# Sheet_1.net
KiCad netlist of a schematic drawn in EasyEDA
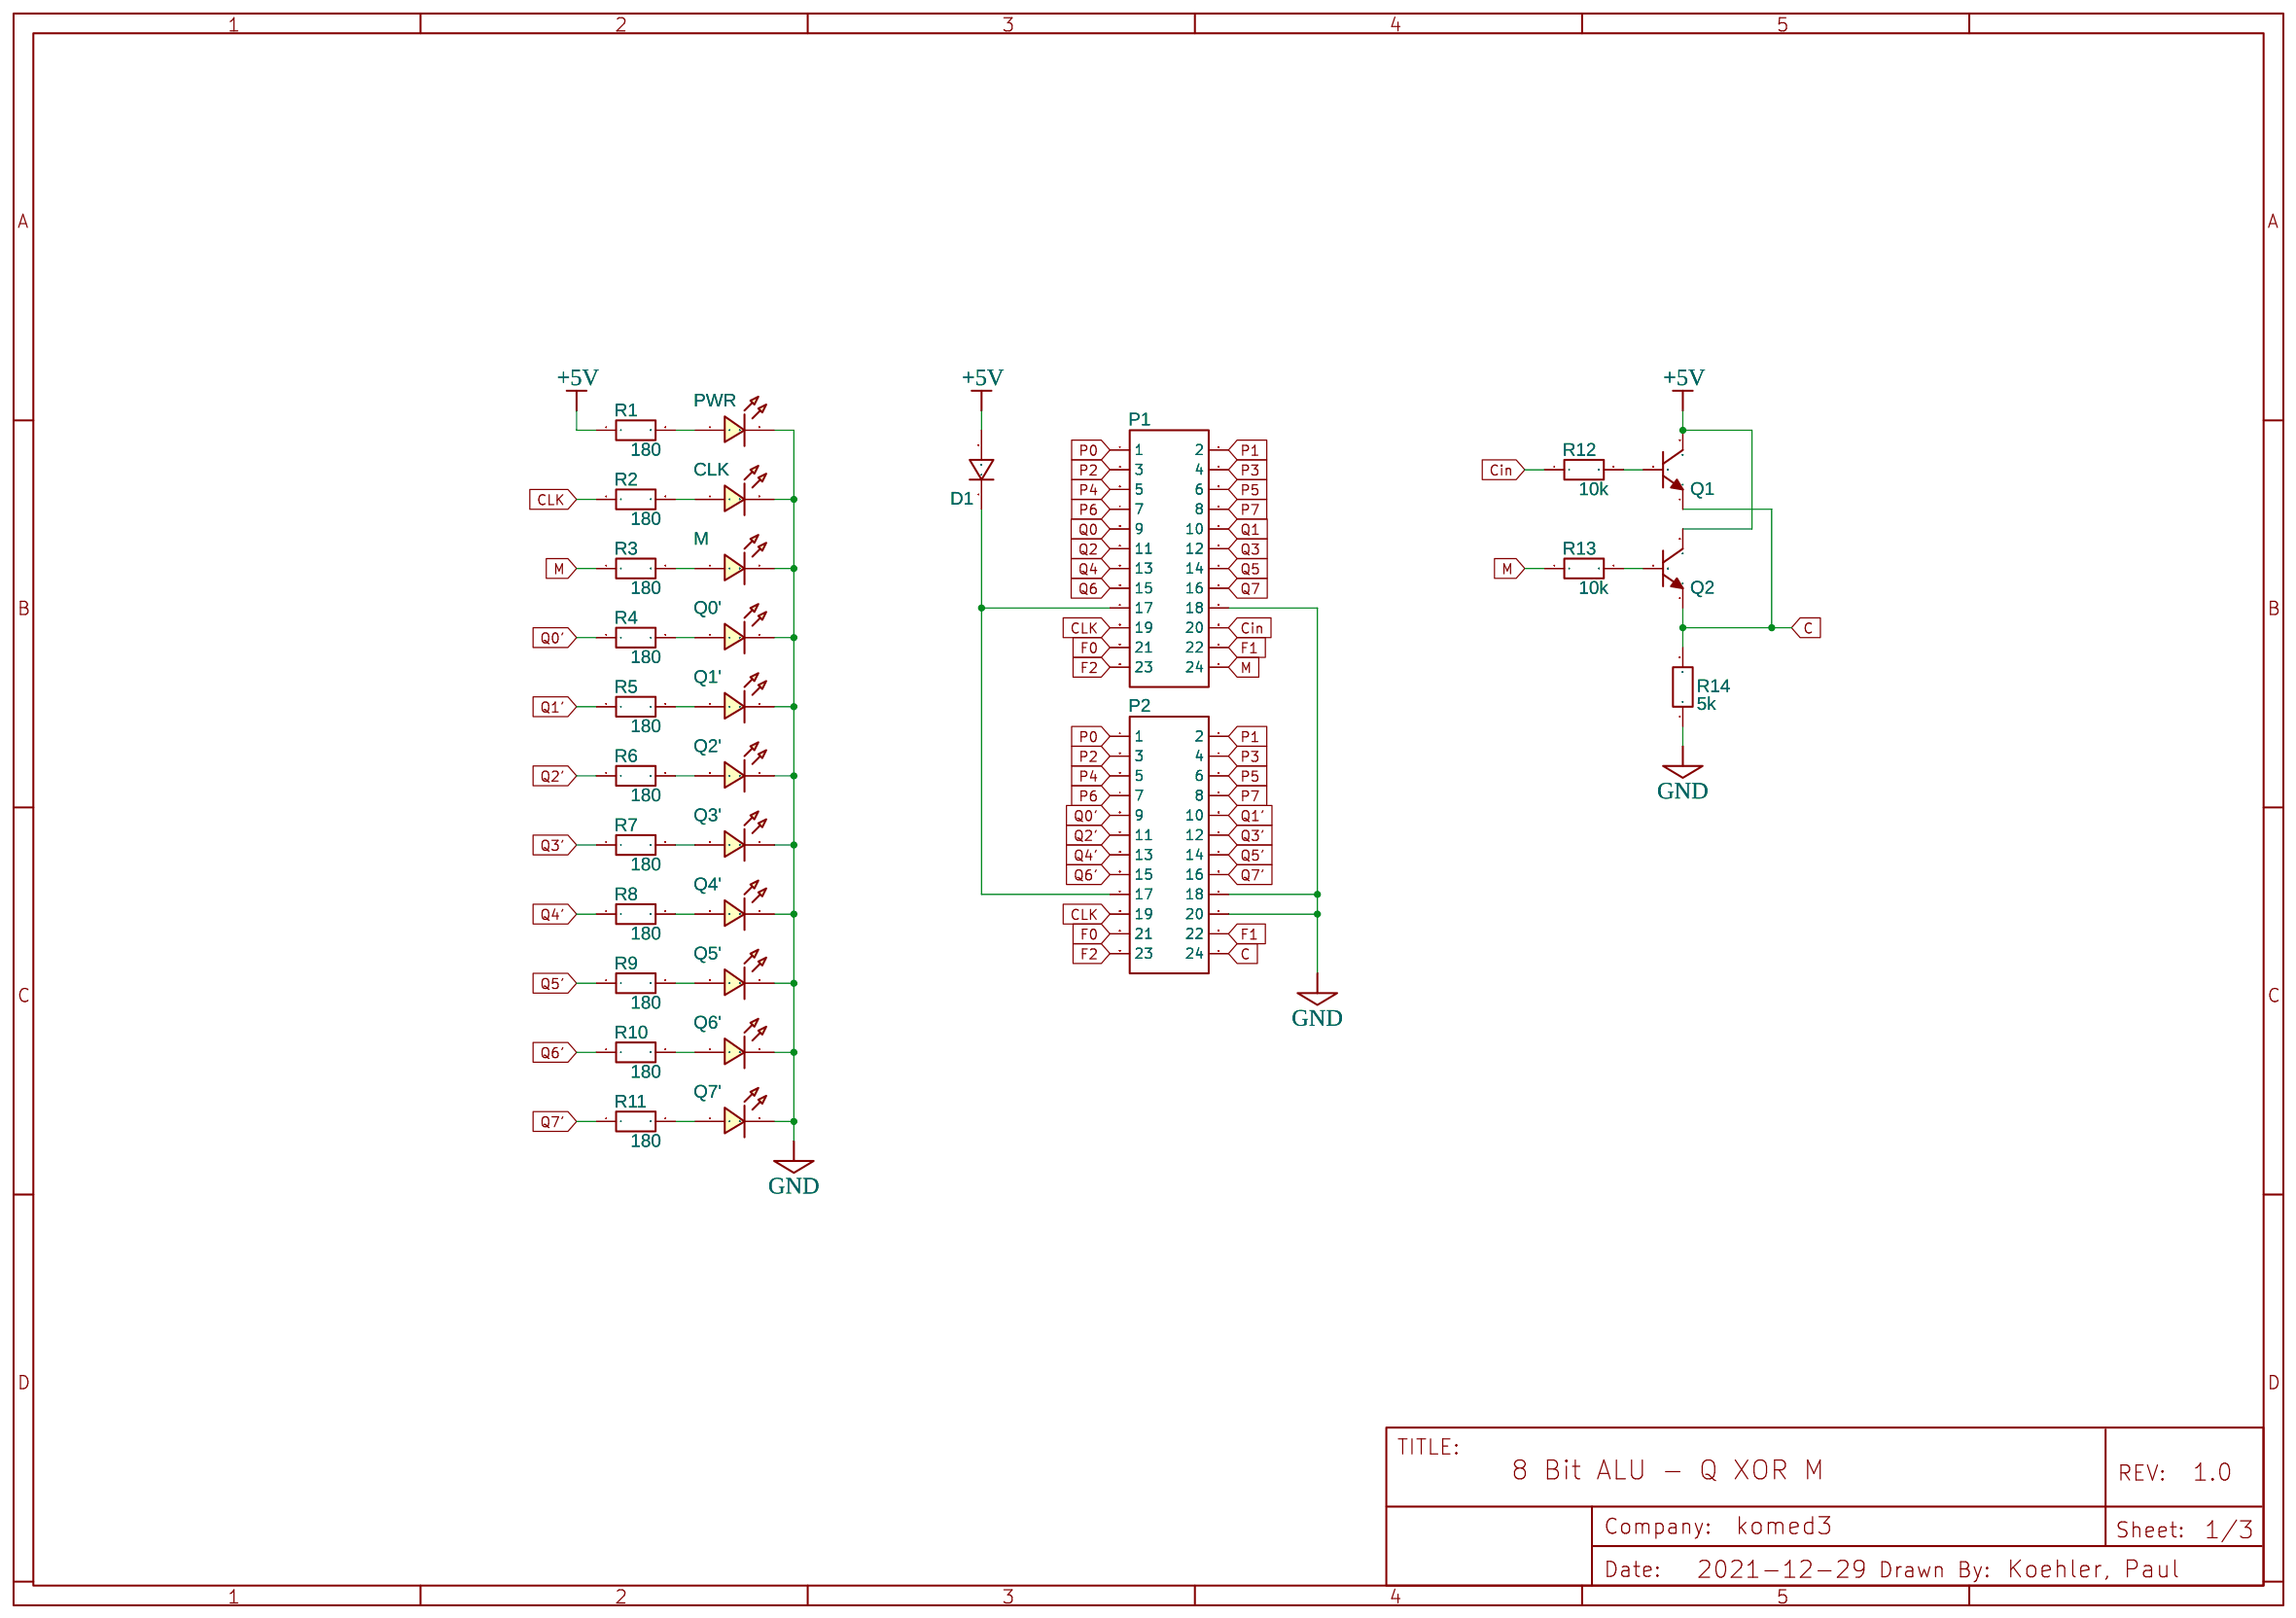
[diagram p0: schematic sheet]

(export (version "E")
  (design (tool "Eeschema 10.0.6"))
  (components
    (comp (ref "CLK")
      (value "LED-TH-5mm_R")
      (fields
        (field (name "BOM_Manufacturer Part") "333-2SURD/S530-A3")
        (field (name "BOM_Supplier Part") "C87271")
      )
      (libsource (lib "") (part "LED-TH-5mm_R_4"))
    )
    (comp (ref "D1")
      (value "1N4007")
      (fields (field (name "BOM_Supplier Part") "C106903"))
      (libsource (lib "") (part "1N4007"))
    )
    (comp (ref "M")
      (value "LED-TH-5mm_R")
      (fields
        (field (name "BOM_Manufacturer Part") "333-2SURD/S530-A3")
        (field (name "BOM_Supplier Part") "C87271")
      )
      (libsource (lib "") (part "LED-TH-5mm_R_1"))
    )
    (comp (ref "P1")
      (value "HDR-IDC-2.54-2X12P")
      (fields
        (field (name "BOM_Manufacturer Part") "IDC Box 2X12 2.54MM")
        (field (name "BOM_Supplier Part") "C9137")
      )
      (libsource (lib "") (part "HDR-IDC-2.54-2X12P"))
    )
    (comp (ref "P2")
      (value "HDR-IDC-2.54-2X12P")
      (fields
        (field (name "BOM_Manufacturer Part") "IDC Box 2X12 2.54MM")
        (field (name "BOM_Supplier Part") "C9137")
      )
      (libsource (lib "") (part "HDR-IDC-2.54-2X12P"))
    )
    (comp (ref "PWR")
      (value "LED-TH-5mm_R")
      (fields
        (field (name "BOM_Manufacturer Part") "333-2SURD/S530-A3")
        (field (name "BOM_Supplier Part") "C87271")
      )
      (libsource (lib "") (part "LED-TH-5mm_R_10"))
    )
    (comp (ref "Q0'")
      (value "LED-TH-5mm_R")
      (fields
        (field (name "BOM_Manufacturer Part") "333-2SURD/S530-A3")
        (field (name "BOM_Supplier Part") "C87271")
      )
      (libsource (lib "") (part "LED-TH-5mm_R_9"))
    )
    (comp (ref "Q1")
      (value "2N3904(TO-92)")
      (fields (field (name "BOM_Manufacturer Part") "2N3904") (field (name "BOM_Supplier Part") "C118538"))
      (libsource (lib "") (part "2N3904(TO-92)"))
    )
    (comp (ref "Q1'")
      (value "LED-TH-5mm_R")
      (fields
        (field (name "BOM_Manufacturer Part") "333-2SURD/S530-A3")
        (field (name "BOM_Supplier Part") "C87271")
      )
      (libsource (lib "") (part "LED-TH-5mm_R_3"))
    )
    (comp (ref "Q2")
      (value "2N3904(TO-92)")
      (fields (field (name "BOM_Manufacturer Part") "2N3904") (field (name "BOM_Supplier Part") "C118538"))
      (libsource (lib "") (part "2N3904(TO-92)"))
    )
    (comp (ref "Q2'")
      (value "LED-TH-5mm_R")
      (fields
        (field (name "BOM_Manufacturer Part") "333-2SURD/S530-A3")
        (field (name "BOM_Supplier Part") "C87271")
      )
      (libsource (lib "") (part "LED-TH-5mm_R_8"))
    )
    (comp (ref "Q3'")
      (value "LED-TH-5mm_R")
      (fields
        (field (name "BOM_Manufacturer Part") "333-2SURD/S530-A3")
        (field (name "BOM_Supplier Part") "C87271")
      )
      (libsource (lib "") (part "LED-TH-5mm_R"))
    )
    (comp (ref "Q4'")
      (value "LED-TH-5mm_R")
      (fields
        (field (name "BOM_Manufacturer Part") "333-2SURD/S530-A3")
        (field (name "BOM_Supplier Part") "C87271")
      )
      (libsource (lib "") (part "LED-TH-5mm_R_5"))
    )
    (comp (ref "Q5'")
      (value "LED-TH-5mm_R")
      (fields
        (field (name "BOM_Manufacturer Part") "333-2SURD/S530-A3")
        (field (name "BOM_Supplier Part") "C87271")
      )
      (libsource (lib "") (part "LED-TH-5mm_R_6"))
    )
    (comp (ref "Q6'")
      (value "LED-TH-5mm_R")
      (fields
        (field (name "BOM_Manufacturer Part") "333-2SURD/S530-A3")
        (field (name "BOM_Supplier Part") "C87271")
      )
      (libsource (lib "") (part "LED-TH-5mm_R_2"))
    )
    (comp (ref "Q7'")
      (value "LED-TH-5mm_R")
      (fields
        (field (name "BOM_Manufacturer Part") "333-2SURD/S530-A3")
        (field (name "BOM_Supplier Part") "C87271")
      )
      (libsource (lib "") (part "LED-TH-5mm_R_7"))
    )
    (comp (ref "R1") (value "180") (libsource (lib "") (part "R_AXIAL-0.3_EU")))
    (comp (ref "R2") (value "180") (libsource (lib "") (part "R_AXIAL-0.3_EU")))
    (comp (ref "R3") (value "180") (libsource (lib "") (part "R_AXIAL-0.3_EU")))
    (comp (ref "R4") (value "180") (libsource (lib "") (part "R_AXIAL-0.3_EU")))
    (comp (ref "R5") (value "180") (libsource (lib "") (part "R_AXIAL-0.3_EU")))
    (comp (ref "R6") (value "180") (libsource (lib "") (part "R_AXIAL-0.3_EU")))
    (comp (ref "R7") (value "180") (libsource (lib "") (part "R_AXIAL-0.3_EU")))
    (comp (ref "R8") (value "180") (libsource (lib "") (part "R_AXIAL-0.3_EU")))
    (comp (ref "R9") (value "180") (libsource (lib "") (part "R_AXIAL-0.3_EU")))
    (comp (ref "R10") (value "180") (libsource (lib "") (part "R_AXIAL-0.3_EU")))
    (comp (ref "R11") (value "180") (libsource (lib "") (part "R_AXIAL-0.3_EU")))
    (comp (ref "R12") (value "10k") (libsource (lib "") (part "R_AXIAL-0.3_EU")))
    (comp (ref "R13") (value "10k") (libsource (lib "") (part "R_AXIAL-0.3_EU")))
    (comp (ref "R14") (value "5k") (libsource (lib "") (part "R_AXIAL-0.3_EU_1")))
  )
  (nets
    (net (code "1") (name "+5V") (class "Default")
      (node (ref "D1") (pin "2") (pinfunction "2_2") (pintype "unspecified"))
      (node (ref "Q1") (pin "3") (pinfunction "C_3") (pintype "unspecified"))
      (node (ref "Q2") (pin "3") (pinfunction "C_3") (pintype "unspecified"))
      (node (ref "R1") (pin "1") (pinfunction "1_1") (pintype "unspecified"))
    )
    (net (code "2") (name "C") (class "Default")
      (node (ref "P2") (pin "24") (pinfunction "24_24") (pintype "unspecified"))
      (node (ref "Q1") (pin "1") (pinfunction "E_1") (pintype "unspecified"))
      (node (ref "Q2") (pin "1") (pinfunction "E_1") (pintype "unspecified"))
      (node (ref "R14") (pin "2") (pinfunction "2_2") (pintype "unspecified"))
    )
    (net (code "3") (name "CLK") (class "Default")
      (node (ref "P1") (pin "19") (pinfunction "19_19") (pintype "unspecified"))
      (node (ref "P2") (pin "19") (pinfunction "19_19") (pintype "unspecified"))
      (node (ref "R2") (pin "1") (pinfunction "1_1") (pintype "unspecified"))
    )
    (net (code "4") (name "Cin") (class "Default")
      (node (ref "P1") (pin "20") (pinfunction "20_20") (pintype "unspecified"))
      (node (ref "R12") (pin "1") (pinfunction "1_1") (pintype "unspecified"))
    )
    (net (code "5") (name "F0") (class "Default")
      (node (ref "P1") (pin "21") (pinfunction "21_21") (pintype "unspecified"))
      (node (ref "P2") (pin "21") (pinfunction "21_21") (pintype "unspecified"))
    )
    (net (code "6") (name "F1") (class "Default")
      (node (ref "P1") (pin "22") (pinfunction "22_22") (pintype "unspecified"))
      (node (ref "P2") (pin "22") (pinfunction "22_22") (pintype "unspecified"))
    )
    (net (code "7") (name "F2") (class "Default")
      (node (ref "P1") (pin "23") (pinfunction "23_23") (pintype "unspecified"))
      (node (ref "P2") (pin "23") (pinfunction "23_23") (pintype "unspecified"))
    )
    (net (code "8") (name "GND") (class "Default")
      (node (ref "CLK") (pin "2") (pinfunction "2_2") (pintype "unspecified"))
      (node (ref "M") (pin "2") (pinfunction "2_2") (pintype "unspecified"))
      (node (ref "P1") (pin "18") (pinfunction "18_18") (pintype "unspecified"))
      (node (ref "P2") (pin "18") (pinfunction "18_18") (pintype "unspecified"))
      (node (ref "P2") (pin "20") (pinfunction "20_20") (pintype "unspecified"))
      (node (ref "PWR") (pin "2") (pinfunction "2_2") (pintype "unspecified"))
      (node (ref "Q0'") (pin "2") (pinfunction "2_2") (pintype "unspecified"))
      (node (ref "Q1'") (pin "2") (pinfunction "2_2") (pintype "unspecified"))
      (node (ref "Q2'") (pin "2") (pinfunction "2_2") (pintype "unspecified"))
      (node (ref "Q3'") (pin "2") (pinfunction "2_2") (pintype "unspecified"))
      (node (ref "Q4'") (pin "2") (pinfunction "2_2") (pintype "unspecified"))
      (node (ref "Q5'") (pin "2") (pinfunction "2_2") (pintype "unspecified"))
      (node (ref "Q6'") (pin "2") (pinfunction "2_2") (pintype "unspecified"))
      (node (ref "Q7'") (pin "2") (pinfunction "2_2") (pintype "unspecified"))
      (node (ref "R14") (pin "1") (pinfunction "1_1") (pintype "unspecified"))
    )
    (net (code "9") (name "M") (class "Default")
      (node (ref "P1") (pin "24") (pinfunction "24_24") (pintype "unspecified"))
      (node (ref "R13") (pin "1") (pinfunction "1_1") (pintype "unspecified"))
      (node (ref "R3") (pin "1") (pinfunction "1_1") (pintype "unspecified"))
    )
    (net (code "10") (name "Net-(CLK-Pad1)") (class "Default")
      (node (ref "CLK") (pin "1") (pinfunction "1_1") (pintype "unspecified"))
      (node (ref "R2") (pin "2") (pinfunction "2_2") (pintype "unspecified"))
    )
    (net (code "11") (name "Net-(D1-Pad1)") (class "Default")
      (node (ref "D1") (pin "1") (pinfunction "1_1") (pintype "unspecified"))
      (node (ref "P1") (pin "17") (pinfunction "17_17") (pintype "unspecified"))
      (node (ref "P2") (pin "17") (pinfunction "17_17") (pintype "unspecified"))
    )
    (net (code "12") (name "Net-(M-Pad1)") (class "Default")
      (node (ref "M") (pin "1") (pinfunction "1_1") (pintype "unspecified"))
      (node (ref "R3") (pin "2") (pinfunction "2_2") (pintype "unspecified"))
    )
    (net (code "13") (name "Net-(PWR-Pad1)") (class "Default")
      (node (ref "PWR") (pin "1") (pinfunction "1_1") (pintype "unspecified"))
      (node (ref "R1") (pin "2") (pinfunction "2_2") (pintype "unspecified"))
    )
    (net (code "14") (name "Net-(Q0'-Pad1)") (class "Default")
      (node (ref "Q0'") (pin "1") (pinfunction "1_1") (pintype "unspecified"))
      (node (ref "R4") (pin "2") (pinfunction "2_2") (pintype "unspecified"))
    )
    (net (code "15") (name "Net-(Q1'-Pad1)") (class "Default")
      (node (ref "Q1'") (pin "1") (pinfunction "1_1") (pintype "unspecified"))
      (node (ref "R5") (pin "2") (pinfunction "2_2") (pintype "unspecified"))
    )
    (net (code "16") (name "Net-(Q1-B)") (class "Default")
      (node (ref "Q1") (pin "2") (pinfunction "B_2") (pintype "unspecified"))
      (node (ref "R12") (pin "2") (pinfunction "2_2") (pintype "unspecified"))
    )
    (net (code "17") (name "Net-(Q2'-Pad1)") (class "Default")
      (node (ref "Q2'") (pin "1") (pinfunction "1_1") (pintype "unspecified"))
      (node (ref "R6") (pin "2") (pinfunction "2_2") (pintype "unspecified"))
    )
    (net (code "18") (name "Net-(Q2-B)") (class "Default")
      (node (ref "Q2") (pin "2") (pinfunction "B_2") (pintype "unspecified"))
      (node (ref "R13") (pin "2") (pinfunction "2_2") (pintype "unspecified"))
    )
    (net (code "19") (name "Net-(Q3'-Pad1)") (class "Default")
      (node (ref "Q3'") (pin "1") (pinfunction "1_1") (pintype "unspecified"))
      (node (ref "R7") (pin "2") (pinfunction "2_2") (pintype "unspecified"))
    )
    (net (code "20") (name "Net-(Q4'-Pad1)") (class "Default")
      (node (ref "Q4'") (pin "1") (pinfunction "1_1") (pintype "unspecified"))
      (node (ref "R8") (pin "2") (pinfunction "2_2") (pintype "unspecified"))
    )
    (net (code "21") (name "Net-(Q5'-Pad1)") (class "Default")
      (node (ref "Q5'") (pin "1") (pinfunction "1_1") (pintype "unspecified"))
      (node (ref "R9") (pin "2") (pinfunction "2_2") (pintype "unspecified"))
    )
    (net (code "22") (name "Net-(Q6'-Pad1)") (class "Default")
      (node (ref "Q6'") (pin "1") (pinfunction "1_1") (pintype "unspecified"))
      (node (ref "R10") (pin "2") (pinfunction "2_2") (pintype "unspecified"))
    )
    (net (code "23") (name "Net-(Q7'-Pad1)") (class "Default")
      (node (ref "Q7'") (pin "1") (pinfunction "1_1") (pintype "unspecified"))
      (node (ref "R11") (pin "2") (pinfunction "2_2") (pintype "unspecified"))
    )
    (net (code "24") (name "P0") (class "Default")
      (node (ref "P1") (pin "1") (pinfunction "1_1") (pintype "unspecified"))
      (node (ref "P2") (pin "1") (pinfunction "1_1") (pintype "unspecified"))
    )
    (net (code "25") (name "P1") (class "Default")
      (node (ref "P1") (pin "2") (pinfunction "2_2") (pintype "unspecified"))
      (node (ref "P2") (pin "2") (pinfunction "2_2") (pintype "unspecified"))
    )
    (net (code "26") (name "P2") (class "Default")
      (node (ref "P1") (pin "3") (pinfunction "3_3") (pintype "unspecified"))
      (node (ref "P2") (pin "3") (pinfunction "3_3") (pintype "unspecified"))
    )
    (net (code "27") (name "P3") (class "Default")
      (node (ref "P1") (pin "4") (pinfunction "4_4") (pintype "unspecified"))
      (node (ref "P2") (pin "4") (pinfunction "4_4") (pintype "unspecified"))
    )
    (net (code "28") (name "P4") (class "Default")
      (node (ref "P1") (pin "5") (pinfunction "5_5") (pintype "unspecified"))
      (node (ref "P2") (pin "5") (pinfunction "5_5") (pintype "unspecified"))
    )
    (net (code "29") (name "P5") (class "Default")
      (node (ref "P1") (pin "6") (pinfunction "6_6") (pintype "unspecified"))
      (node (ref "P2") (pin "6") (pinfunction "6_6") (pintype "unspecified"))
    )
    (net (code "30") (name "P6") (class "Default")
      (node (ref "P1") (pin "7") (pinfunction "7_7") (pintype "unspecified"))
      (node (ref "P2") (pin "7") (pinfunction "7_7") (pintype "unspecified"))
    )
    (net (code "31") (name "P7") (class "Default")
      (node (ref "P1") (pin "8") (pinfunction "8_8") (pintype "unspecified"))
      (node (ref "P2") (pin "8") (pinfunction "8_8") (pintype "unspecified"))
    )
    (net (code "32") (name "Q0") (class "Default")
      (node (ref "P1") (pin "9") (pinfunction "9_9") (pintype "unspecified"))
    )
    (net (code "33") (name "Q0'") (class "Default")
      (node (ref "P2") (pin "9") (pinfunction "9_9") (pintype "unspecified"))
      (node (ref "R4") (pin "1") (pinfunction "1_1") (pintype "unspecified"))
    )
    (net (code "34") (name "Q1") (class "Default")
      (node (ref "P1") (pin "10") (pinfunction "10_10") (pintype "unspecified"))
    )
    (net (code "35") (name "Q1'") (class "Default")
      (node (ref "P2") (pin "10") (pinfunction "10_10") (pintype "unspecified"))
      (node (ref "R5") (pin "1") (pinfunction "1_1") (pintype "unspecified"))
    )
    (net (code "36") (name "Q2") (class "Default")
      (node (ref "P1") (pin "11") (pinfunction "11_11") (pintype "unspecified"))
    )
    (net (code "37") (name "Q2'") (class "Default")
      (node (ref "P2") (pin "11") (pinfunction "11_11") (pintype "unspecified"))
      (node (ref "R6") (pin "1") (pinfunction "1_1") (pintype "unspecified"))
    )
    (net (code "38") (name "Q3") (class "Default")
      (node (ref "P1") (pin "12") (pinfunction "12_12") (pintype "unspecified"))
    )
    (net (code "39") (name "Q3'") (class "Default")
      (node (ref "P2") (pin "12") (pinfunction "12_12") (pintype "unspecified"))
      (node (ref "R7") (pin "1") (pinfunction "1_1") (pintype "unspecified"))
    )
    (net (code "40") (name "Q4") (class "Default")
      (node (ref "P1") (pin "13") (pinfunction "13_13") (pintype "unspecified"))
    )
    (net (code "41") (name "Q4'") (class "Default")
      (node (ref "P2") (pin "13") (pinfunction "13_13") (pintype "unspecified"))
      (node (ref "R8") (pin "1") (pinfunction "1_1") (pintype "unspecified"))
    )
    (net (code "42") (name "Q5") (class "Default")
      (node (ref "P1") (pin "14") (pinfunction "14_14") (pintype "unspecified"))
    )
    (net (code "43") (name "Q5'") (class "Default")
      (node (ref "P2") (pin "14") (pinfunction "14_14") (pintype "unspecified"))
      (node (ref "R9") (pin "1") (pinfunction "1_1") (pintype "unspecified"))
    )
    (net (code "44") (name "Q6") (class "Default")
      (node (ref "P1") (pin "15") (pinfunction "15_15") (pintype "unspecified"))
    )
    (net (code "45") (name "Q6'") (class "Default")
      (node (ref "P2") (pin "15") (pinfunction "15_15") (pintype "unspecified"))
      (node (ref "R10") (pin "1") (pinfunction "1_1") (pintype "unspecified"))
    )
    (net (code "46") (name "Q7") (class "Default")
      (node (ref "P1") (pin "16") (pinfunction "16_16") (pintype "unspecified"))
    )
    (net (code "47") (name "Q7'") (class "Default")
      (node (ref "P2") (pin "16") (pinfunction "16_16") (pintype "unspecified"))
      (node (ref "R11") (pin "1") (pinfunction "1_1") (pintype "unspecified"))
    )
  )
)
